# REGENIX_TITLE.net
KiCad netlist of a schematic drawn in Altium Designer
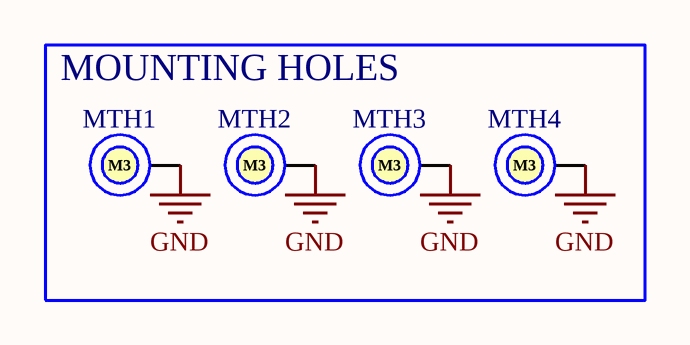
[diagram p0: REGENIX_TITLE.SchDoc]

(export (version "E")
  (design (tool "Eeschema 10.0.6"))
  (components
    (comp (ref "MTH1")
      (value "M3")
      (footprint "MTH_M3")
      (description "MTH - MOUNTING HOLE M3 PLATED - M3")
      (fields
        (field (name "CREATEDBY/DATE") "Jonathan Bouchard 2018-07-23")
        (field (name "VERIFIEDBY") "Arnaud Samson 23-07-18")
      )
      (libsource (lib "S7CAS_LIB2023") (part "MTH_M3"))
    )
    (comp (ref "MTH2")
      (value "M3")
      (footprint "MTH_M3")
      (description "MTH - MOUNTING HOLE M3 PLATED - M3")
      (fields
        (field (name "CREATEDBY/DATE") "Jonathan Bouchard 2018-07-23")
        (field (name "VERIFIEDBY") "Arnaud Samson 23-07-18")
      )
      (libsource (lib "S7CAS_LIB2023") (part "MTH_M3"))
    )
    (comp (ref "MTH3")
      (value "M3")
      (footprint "MTH_M3")
      (description "MTH - MOUNTING HOLE M3 PLATED - M3")
      (fields
        (field (name "CREATEDBY/DATE") "Jonathan Bouchard 2018-07-23")
        (field (name "VERIFIEDBY") "Arnaud Samson 23-07-18")
      )
      (libsource (lib "S7CAS_LIB2023") (part "MTH_M3"))
    )
    (comp (ref "MTH4")
      (value "M3")
      (footprint "MTH_M3")
      (description "MTH - MOUNTING HOLE M3 PLATED - M3")
      (fields
        (field (name "CREATEDBY/DATE") "Jonathan Bouchard 2018-07-23")
        (field (name "VERIFIEDBY") "Arnaud Samson 23-07-18")
      )
      (libsource (lib "S7CAS_LIB2023") (part "MTH_M3"))
    )
  )
  (nets
    (net (code "1") (name "GND") (class "Default")
      (node (ref "MTH1") (pin "1") (pinfunction "1_1") (pintype "passive"))
      (node (ref "MTH2") (pin "1") (pinfunction "1_1") (pintype "passive"))
      (node (ref "MTH3") (pin "1") (pinfunction "1_1") (pintype "passive"))
      (node (ref "MTH4") (pin "1") (pinfunction "1_1") (pintype "passive"))
    )
  )
)
